# OCTOSPI_FLASH.net
KiCad netlist of a schematic drawn in Altium Designer
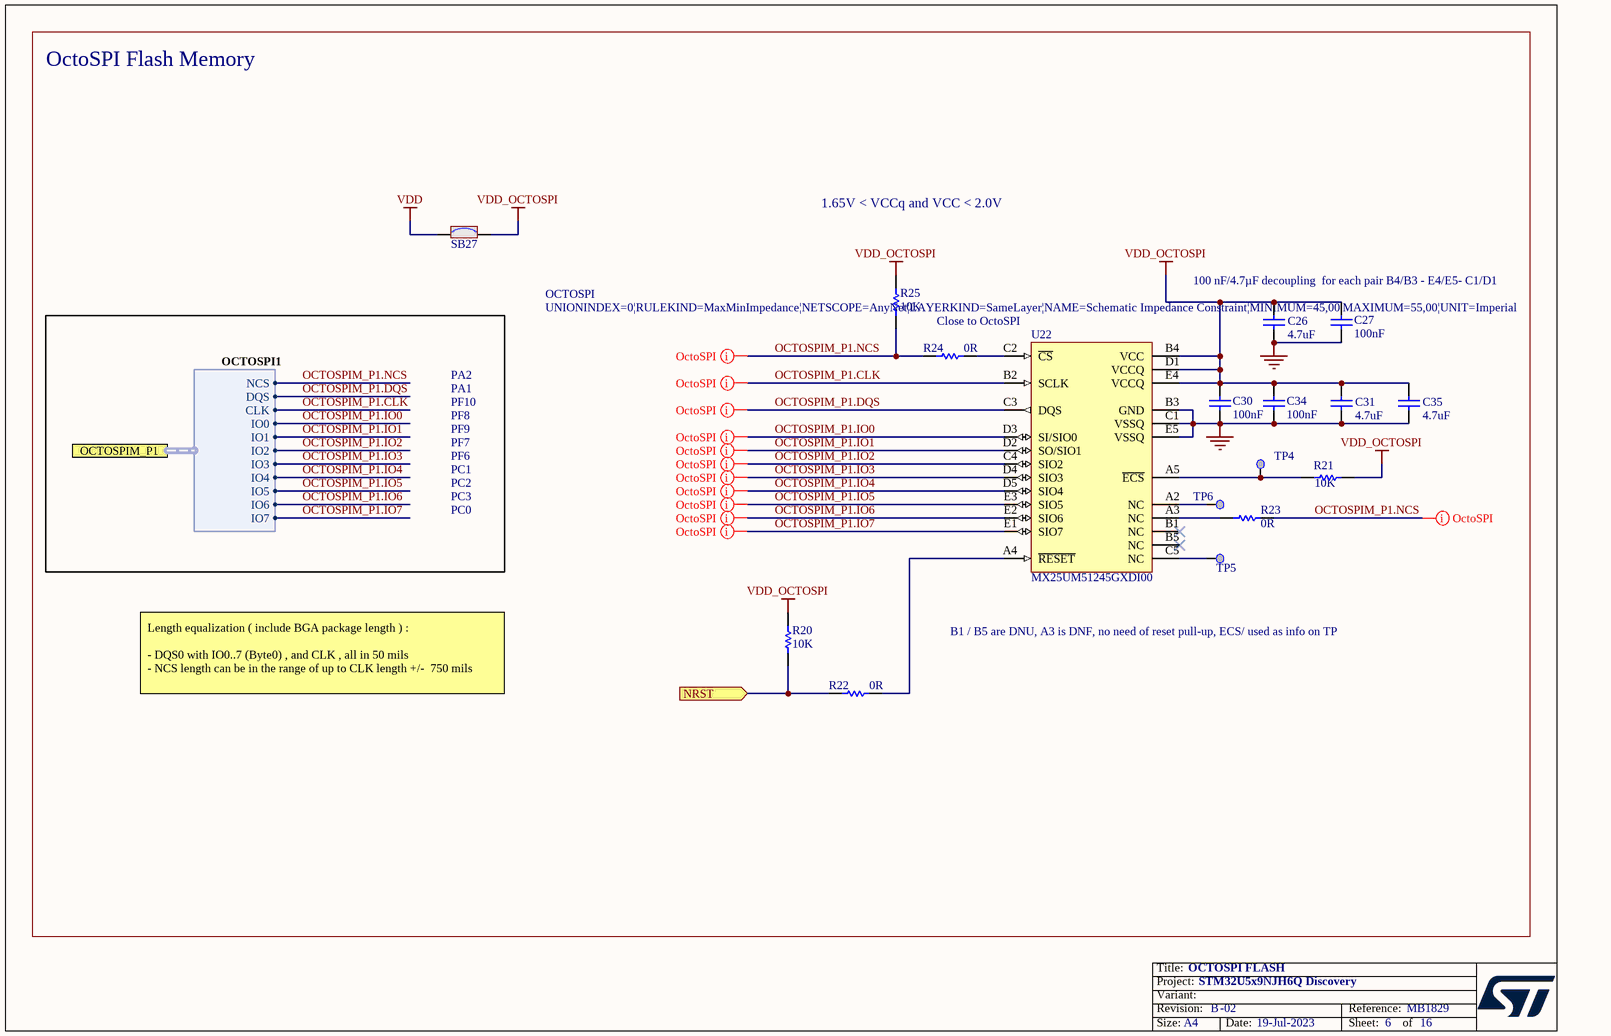
[diagram p0: OCTOSPI_FLASH.SchDoc]

(export (version "E")
  (design (tool "Eeschema 10.0.6"))
  (components
    (comp (ref "C26")
      (value "4.7uF")
      (footprint "MCD_PARTS:C0603")
      (description "Capacitor, MLCC, 4.7uF, 16V, X5R, +/-10%, 0603, T=0.8mm")
      (fields
        (field (name "INTERNAL_PART_NUMBER") "MCD-00009")
        (field (name "MANUFACTURER_PART_NUMBER") "CC0603KRX5R7BB475")
      )
      (libsource (lib "MCD_PARTS_database") (part "Capacitor"))
    )
    (comp (ref "C27")
      (value "100nF")
      (footprint "MCD_PARTS:C0402")
      (description "Capacitor, MLCC, 100nF, 16V, X7R, +/-10%, 0402, T=0.5mm")
      (fields
        (field (name "INTERNAL_PART_NUMBER") "MCD-00006")
        (field (name "MANUFACTURER_PART_NUMBER") "CC0402KRX7R7BB104")
      )
      (libsource (lib "MCD_PARTS_database") (part "Capacitor"))
    )
    (comp (ref "C30")
      (value "100nF")
      (footprint "MCD_PARTS:C0402")
      (description "Capacitor, MLCC, 100nF, 16V, X7R, +/-10%, 0402, T=0.5mm")
      (fields
        (field (name "INTERNAL_PART_NUMBER") "MCD-00006")
        (field (name "MANUFACTURER_PART_NUMBER") "CC0402KRX7R7BB104")
      )
      (libsource (lib "MCD_PARTS_database") (part "Capacitor"))
    )
    (comp (ref "C31")
      (value "4.7uF")
      (footprint "MCD_PARTS:C0603")
      (description "Capacitor, MLCC, 4.7uF, 16V, X5R, +/-10%, 0603, T=0.8mm")
      (fields
        (field (name "INTERNAL_PART_NUMBER") "MCD-00009")
        (field (name "MANUFACTURER_PART_NUMBER") "CC0603KRX5R7BB475")
      )
      (libsource (lib "MCD_PARTS_database") (part "Capacitor"))
    )
    (comp (ref "C34")
      (value "100nF")
      (footprint "MCD_PARTS:C0402")
      (description "Capacitor, MLCC, 100nF, 16V, X7R, +/-10%, 0402, T=0.5mm")
      (fields
        (field (name "INTERNAL_PART_NUMBER") "MCD-00006")
        (field (name "MANUFACTURER_PART_NUMBER") "CC0402KRX7R7BB104")
      )
      (libsource (lib "MCD_PARTS_database") (part "Capacitor"))
    )
    (comp (ref "C35")
      (value "4.7uF")
      (footprint "MCD_PARTS:C0603")
      (description "Capacitor, MLCC, 4.7uF, 16V, X5R, +/-10%, 0603, T=0.8mm")
      (fields
        (field (name "INTERNAL_PART_NUMBER") "MCD-00009")
        (field (name "MANUFACTURER_PART_NUMBER") "CC0603KRX5R7BB475")
      )
      (libsource (lib "MCD_PARTS_database") (part "Capacitor"))
    )
    (comp (ref "R20")
      (value "10K")
      (footprint "MCD_PARTS:R0402")
      (description "Resistor, 10K, 0402, +/-1%, 1/16W")
      (fields
        (field (name "INTERNAL_PART_NUMBER") "MCD-00053")
        (field (name "MANUFACTURER_PART_NUMBER") "RC0402FR-0710KL")
      )
      (libsource (lib "MCD_PARTS_database") (part "Resistor"))
    )
    (comp (ref "R21")
      (value "10K")
      (footprint "MCD_PARTS:R0402")
      (description "Resistor, 10K, 0402, +/-1%, 1/16W")
      (fields
        (field (name "INTERNAL_PART_NUMBER") "MCD-00053")
        (field (name "MANUFACTURER_PART_NUMBER") "RC0402FR-0710KL")
      )
      (libsource (lib "MCD_PARTS_database") (part "Resistor"))
    )
    (comp (ref "R22")
      (value "0R")
      (footprint "MCD_PARTS:R0402")
      (description "Resistor, 0R, 0402, +/-5%, 1/16W")
      (fields
        (field (name "INTERNAL_PART_NUMBER") "MCD-00052")
        (field (name "MANUFACTURER_PART_NUMBER") "RC0402JR-070RL")
      )
      (libsource (lib "MCD_PARTS_database") (part "Resistor"))
    )
    (comp (ref "R23")
      (value "0R")
      (footprint "MCD_PARTS:R0402")
      (description "Resistor, 0R, 0402, +/-5%, 1/16W")
      (fields
        (field (name "INTERNAL_PART_NUMBER") "MCD-00052")
        (field (name "MANUFACTURER_PART_NUMBER") "RC0402JR-070RL")
      )
      (libsource (lib "MCD_PARTS_database") (part "Resistor"))
    )
    (comp (ref "R24")
      (value "0R")
      (footprint "MCD_PARTS:R0402")
      (description "Resistor, 0R, 0402, +/-5%, 1/16W")
      (fields
        (field (name "INTERNAL_PART_NUMBER") "MCD-00052")
        (field (name "MANUFACTURER_PART_NUMBER") "RC0402JR-070RL")
      )
      (libsource (lib "MCD_PARTS_database") (part "Resistor"))
    )
    (comp (ref "R25")
      (value "10K")
      (footprint "MCD_PARTS:R0402")
      (description "Resistor, 10K, 0402, +/-1%, 1/16W")
      (fields
        (field (name "INTERNAL_PART_NUMBER") "MCD-00053")
        (field (name "MANUFACTURER_PART_NUMBER") "RC0402FR-0710KL")
      )
      (libsource (lib "MCD_PARTS_database") (part "Resistor"))
    )
    (comp (ref "SB27")
      (value "SB_ON")
      (footprint "MCD_PARTS:SOLDER-BRIDGE_R0402-0R")
      (description "Solder Bridge 0402 ON")
      (fields
        (field (name "INTERNAL_PART_NUMBER") "MCD-01618")
        (field (name "MANUFACTURER_PART_NUMBER") "RC0402JR-070RL")
      )
      (libsource (lib "MCD_PARTS_database") (part "SB_ON"))
    )
    (comp (ref "TP4")
      (value "Test Point")
      (footprint "MCD_PARTS:TP_SMD_1MM")
      (description "Test Point 1mm")
      (fields (field (name "INTERNAL_PART_NUMBER") "MCD-00074"))
      (libsource (lib "") (part "Test Point_1"))
    )
    (comp (ref "TP5")
      (value "Test Point")
      (footprint "MCD_PARTS:TP_SMD_1MM")
      (description "Test Point 1mm")
      (fields (field (name "INTERNAL_PART_NUMBER") "MCD-00074"))
      (libsource (lib "MCD_PARTS_database") (part "Test Point"))
    )
    (comp (ref "TP6")
      (value "Test Point")
      (footprint "MCD_PARTS:TP_SMD_1MM")
      (description "Test Point 1mm")
      (fields (field (name "INTERNAL_PART_NUMBER") "MCD-00074"))
      (libsource (lib "MCD_PARTS_database") (part "Test Point"))
    )
    (comp (ref "U22")
      (value "MX25UM51245GXDI00")
      (footprint "MCD_PARTS:ICC_BGA24_5X5-BALL-ARRAY_6X8_P1")
      (description "Memory,Octo-SPI-NOR,512Mb,x1/x8,133/200MHz,1.8V,DTR,BGA24, CMOS MXSMIO")
      (fields (field (name "INTERNAL_PART_NUMBER") "MCD-02166") (field (name "MANUFACTURER") "MACRONIX"))
      (libsource (lib "MCD_PARTS_database") (part "MX25xx51245GXDx00"))
    )
  )
  (nets
    (net (code "2") (name "/NRST") (class "Default")
      (node (ref "R20") (pin "1") (pinfunction "1_1") (pintype "passive"))
      (node (ref "R22") (pin "1") (pinfunction "1_1") (pintype "passive"))
    )
    (net (code "3") (name "/OCTOSPIM_P1.CLK") (class "Default")
      (node (ref "U22") (pin "B2") (pinfunction "SCLK_B2") (pintype "input"))
    )
    (net (code "4") (name "/OCTOSPIM_P1.DQS") (class "Default")
      (node (ref "U22") (pin "C3") (pinfunction "DQS_C3") (pintype "output"))
    )
    (net (code "5") (name "/OCTOSPIM_P1.IO0") (class "Default")
      (node (ref "U22") (pin "D3") (pinfunction "SI/SIO0_D3") (pintype "bidirectional"))
    )
    (net (code "6") (name "/OCTOSPIM_P1.IO1") (class "Default")
      (node (ref "U22") (pin "D2") (pinfunction "SO/SIO1_D2") (pintype "bidirectional"))
    )
    (net (code "7") (name "/OCTOSPIM_P1.IO2") (class "Default")
      (node (ref "U22") (pin "C4") (pinfunction "SIO2_C4") (pintype "bidirectional"))
    )
    (net (code "8") (name "/OCTOSPIM_P1.IO3") (class "Default")
      (node (ref "U22") (pin "D4") (pinfunction "SIO3_D4") (pintype "bidirectional"))
    )
    (net (code "9") (name "/OCTOSPIM_P1.IO4") (class "Default")
      (node (ref "U22") (pin "D5") (pinfunction "SIO4_D5") (pintype "bidirectional"))
    )
    (net (code "10") (name "/OCTOSPIM_P1.IO5") (class "Default")
      (node (ref "U22") (pin "E3") (pinfunction "SIO5_E3") (pintype "bidirectional"))
    )
    (net (code "11") (name "/OCTOSPIM_P1.IO6") (class "Default")
      (node (ref "U22") (pin "E2") (pinfunction "SIO6_E2") (pintype "bidirectional"))
    )
    (net (code "12") (name "/OCTOSPIM_P1.IO7") (class "Default")
      (node (ref "U22") (pin "E1") (pinfunction "SIO7_E1") (pintype "bidirectional"))
    )
    (net (code "13") (name "/OCTOSPIM_P1.NCS") (class "Default")
      (node (ref "R23") (pin "2") (pinfunction "2_2") (pintype "passive"))
      (node (ref "R24") (pin "1") (pinfunction "1_1") (pintype "passive"))
      (node (ref "R25") (pin "1") (pinfunction "1_1") (pintype "passive"))
    )
    (net (code "15") (name "GND") (class "Default")
      (node (ref "C26") (pin "1") (pinfunction "1_1") (pintype "passive"))
      (node (ref "C27") (pin "1") (pinfunction "1_1") (pintype "passive"))
      (node (ref "C30") (pin "1") (pinfunction "1_1") (pintype "passive"))
      (node (ref "C31") (pin "1") (pinfunction "1_1") (pintype "passive"))
      (node (ref "C34") (pin "1") (pinfunction "1_1") (pintype "passive"))
      (node (ref "C35") (pin "1") (pinfunction "1_1") (pintype "passive"))
      (node (ref "U22") (pin "B3") (pinfunction "GND_B3") (pintype "power_in"))
      (node (ref "U22") (pin "C1") (pinfunction "VSSQ_C1") (pintype "power_in"))
      (node (ref "U22") (pin "E5") (pinfunction "VSSQ_E5") (pintype "power_in"))
    )
    (net (code "16") (name "Net-(R23-Pad1)") (class "Default")
      (node (ref "R23") (pin "1") (pinfunction "1_1") (pintype "passive"))
      (node (ref "U22") (pin "A3") (pinfunction "NC_A3") (pintype "passive"))
    )
    (net (code "17") (name "Net-(TP5-Pad1)") (class "Default")
      (node (ref "TP5") (pin "1") (pinfunction "1_1") (pintype "passive"))
      (node (ref "U22") (pin "C5") (pinfunction "NC_C5") (pintype "passive"))
    )
    (net (code "18") (name "Net-(TP6-Pad1)") (class "Default")
      (node (ref "TP6") (pin "1") (pinfunction "1_1") (pintype "passive"))
      (node (ref "U22") (pin "A2") (pinfunction "NC_A2") (pintype "passive"))
    )
    (net (code "19") (name "Net-(U22-~{CS})") (class "Default")
      (node (ref "R24") (pin "2") (pinfunction "2_2") (pintype "passive"))
      (node (ref "U22") (pin "C2") (pinfunction "~{CS}_C2") (pintype "input"))
    )
    (net (code "20") (name "Net-(U22-~{ECS})") (class "Default")
      (node (ref "R21") (pin "1") (pinfunction "1_1") (pintype "passive"))
      (node (ref "TP4") (pin "1") (pinfunction "1_1") (pintype "passive"))
      (node (ref "U22") (pin "A5") (pinfunction "~{ECS}_A5") (pintype "passive"))
    )
    (net (code "21") (name "Net-(U22-~{RESET})") (class "Default")
      (node (ref "R22") (pin "2") (pinfunction "2_2") (pintype "passive"))
      (node (ref "U22") (pin "A4") (pinfunction "~{RESET}_A4") (pintype "input"))
    )
    (net (code "22") (name "VDD") (class "Default")
      (node (ref "SB27") (pin "1") (pinfunction "1_1") (pintype "passive"))
    )
    (net (code "23") (name "VDD_OCTOSPI") (class "Default")
      (node (ref "C26") (pin "2") (pinfunction "2_2") (pintype "passive"))
      (node (ref "C27") (pin "2") (pinfunction "2_2") (pintype "passive"))
      (node (ref "C30") (pin "2") (pinfunction "2_2") (pintype "passive"))
      (node (ref "C31") (pin "2") (pinfunction "2_2") (pintype "passive"))
      (node (ref "C34") (pin "2") (pinfunction "2_2") (pintype "passive"))
      (node (ref "C35") (pin "2") (pinfunction "2_2") (pintype "passive"))
      (node (ref "R20") (pin "2") (pinfunction "2_2") (pintype "passive"))
      (node (ref "R21") (pin "2") (pinfunction "2_2") (pintype "passive"))
      (node (ref "R25") (pin "2") (pinfunction "2_2") (pintype "passive"))
      (node (ref "SB27") (pin "2") (pinfunction "2_2") (pintype "passive"))
      (node (ref "U22") (pin "B4") (pinfunction "VCC_B4") (pintype "power_in"))
      (node (ref "U22") (pin "D1") (pinfunction "VCCQ_D1") (pintype "power_in"))
      (node (ref "U22") (pin "E4") (pinfunction "VCCQ_E4") (pintype "power_in"))
    )
    (net (code "24") (name "unconnected-(U22-NC-PadB1)") (class "Default")
      (node (ref "U22") (pin "B1") (pinfunction "NC_B1") (pintype "passive+no_connect"))
    )
    (net (code "25") (name "unconnected-(U22-NC-PadB5)") (class "Default")
      (node (ref "U22") (pin "B5") (pinfunction "NC_B5") (pintype "passive+no_connect"))
    )
  )
)
